# ArmBoard.net
KiCad netlist of a schematic drawn in Altium Designer
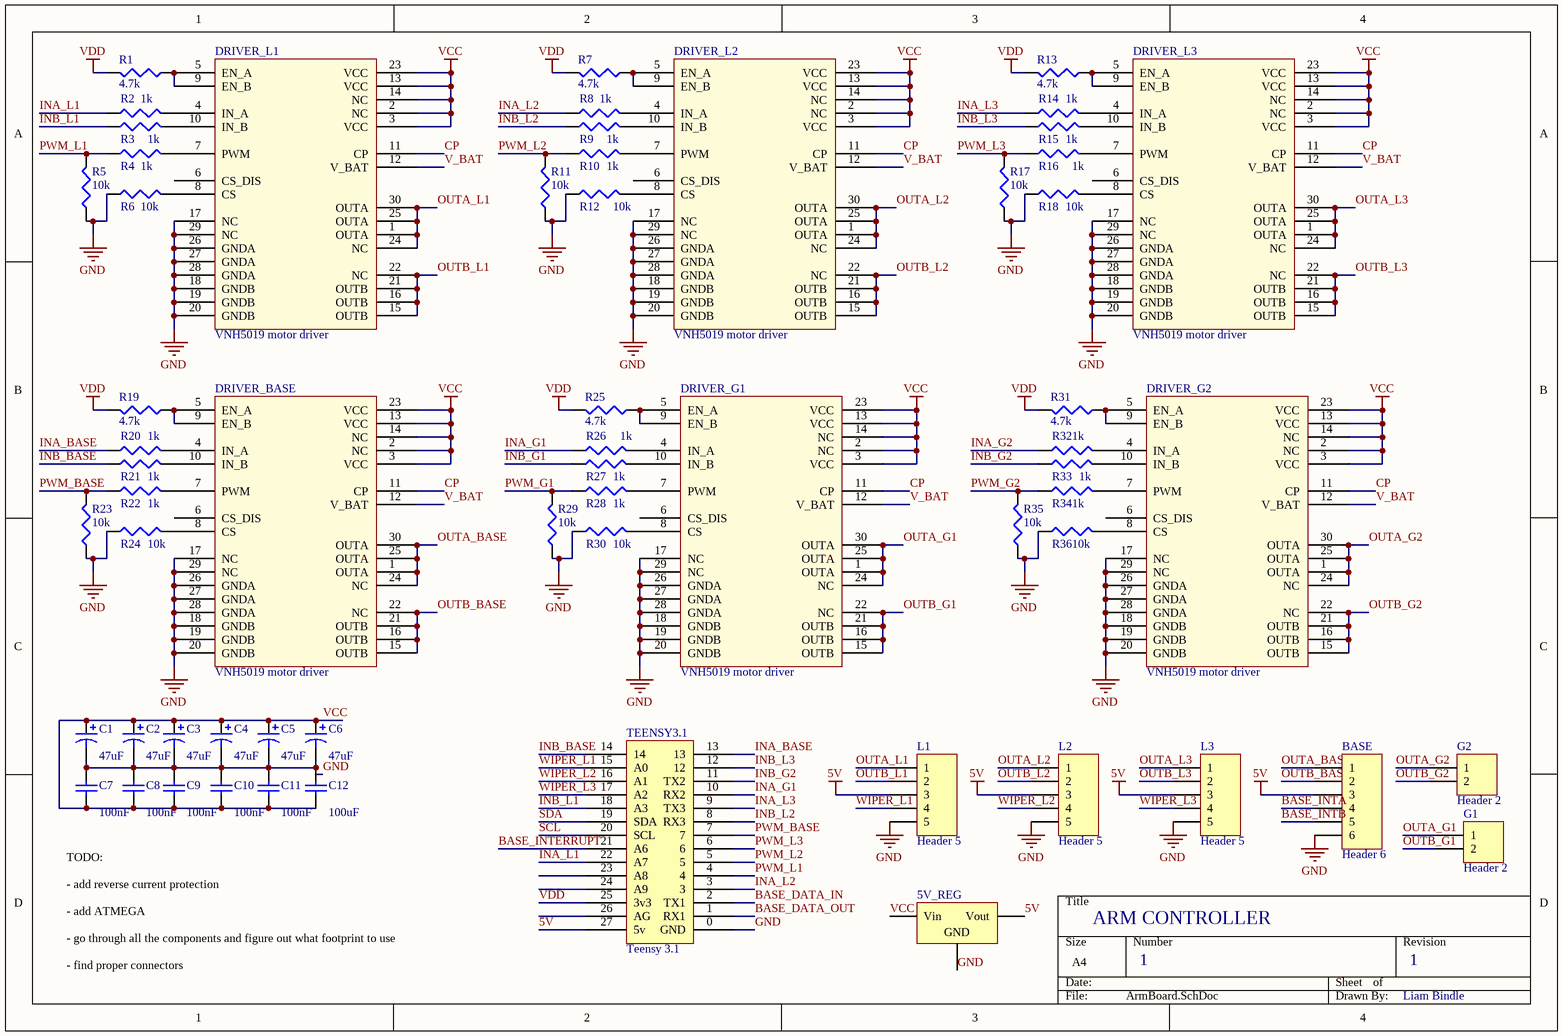
[diagram p0: ArmBoard.SchDoc]

(export (version "E")
  (design (tool "Eeschema 10.0.6"))
  (components
    (comp (ref "5V_REG")
      (value "~")
      (footprint "D2PAK_M")
      (description "Voltage Regulator")
      (fields (field (name "PUBLISHER") "Altium Limited"))
      (libsource (lib "Miscellaneous Devices") (part "Volt Reg"))
    )
    (comp (ref "BASE")
      (value "Header 6")
      (footprint "HDR1X6")
      (description "Header, 6-Pin")
      (fields (field (name "PUBLISHER") "Altium Limited"))
      (libsource (lib "Miscellaneous Connectors") (part "Header 6"))
    )
    (comp (ref "C1")
      (value "47uF")
      (footprint "RB7.6-15")
      (description "Polarized Capacitor (Radial)")
      (fields (field (name "PUBLISHER") "Altium Limited"))
      (libsource (lib "Miscellaneous Devices") (part "Cap Pol1"))
    )
    (comp (ref "C2")
      (value "47uF")
      (footprint "RB7.6-15")
      (description "Polarized Capacitor (Radial)")
      (fields (field (name "PUBLISHER") "Altium Limited"))
      (libsource (lib "Miscellaneous Devices") (part "Cap Pol1"))
    )
    (comp (ref "C3")
      (value "47uF")
      (footprint "RB7.6-15")
      (description "Polarized Capacitor (Radial)")
      (fields (field (name "PUBLISHER") "Altium Limited"))
      (libsource (lib "Miscellaneous Devices") (part "Cap Pol1"))
    )
    (comp (ref "C4")
      (value "47uF")
      (footprint "RB7.6-15")
      (description "Polarized Capacitor (Radial)")
      (fields (field (name "PUBLISHER") "Altium Limited"))
      (libsource (lib "Miscellaneous Devices") (part "Cap Pol1"))
    )
    (comp (ref "C5")
      (value "47uF")
      (footprint "RB7.6-15")
      (description "Polarized Capacitor (Radial)")
      (fields (field (name "PUBLISHER") "Altium Limited"))
      (libsource (lib "Miscellaneous Devices") (part "Cap Pol1"))
    )
    (comp (ref "C6")
      (value "47uF")
      (footprint "RB7.6-15")
      (description "Polarized Capacitor (Radial)")
      (fields (field (name "PUBLISHER") "Altium Limited"))
      (libsource (lib "Miscellaneous Devices") (part "Cap Pol1"))
    )
    (comp (ref "C7")
      (value "100nF")
      (footprint "RAD-0.3")
      (description "Capacitor")
      (fields (field (name "PUBLISHER") "Altium Limited"))
      (libsource (lib "Miscellaneous Devices") (part "Cap"))
    )
    (comp (ref "C8")
      (value "100nF")
      (footprint "RAD-0.3")
      (description "Capacitor")
      (fields (field (name "PUBLISHER") "Altium Limited"))
      (libsource (lib "Miscellaneous Devices") (part "Cap"))
    )
    (comp (ref "C9")
      (value "100nF")
      (footprint "RAD-0.3")
      (description "Capacitor")
      (fields (field (name "PUBLISHER") "Altium Limited"))
      (libsource (lib "Miscellaneous Devices") (part "Cap"))
    )
    (comp (ref "C10")
      (value "100nF")
      (footprint "RAD-0.3")
      (description "Capacitor")
      (fields (field (name "PUBLISHER") "Altium Limited"))
      (libsource (lib "Miscellaneous Devices") (part "Cap"))
    )
    (comp (ref "C11")
      (value "100nF")
      (footprint "RAD-0.3")
      (description "Capacitor")
      (fields (field (name "PUBLISHER") "Altium Limited"))
      (libsource (lib "Miscellaneous Devices") (part "Cap"))
    )
    (comp (ref "C12")
      (value "100uF")
      (footprint "RAD-0.3")
      (description "Capacitor")
      (fields (field (name "PUBLISHER") "Altium Limited"))
      (libsource (lib "Miscellaneous Devices") (part "Cap"))
    )
    (comp (ref "DRIVER_BASE")
      (value "VNH5019 motor driver")
      (footprint "VNH5019")
      (description "Motor driver")
      (libsource (lib "USSTParts") (part "VNH5019"))
    )
    (comp (ref "DRIVER_G1")
      (value "VNH5019 motor driver")
      (footprint "VNH5019")
      (description "Motor driver")
      (libsource (lib "USSTParts") (part "VNH5019"))
    )
    (comp (ref "DRIVER_G2")
      (value "VNH5019 motor driver")
      (footprint "VNH5019")
      (description "Motor driver")
      (libsource (lib "USSTParts") (part "VNH5019"))
    )
    (comp (ref "DRIVER_L1")
      (value "VNH5019 motor driver")
      (footprint "VNH5019")
      (description "Motor driver")
      (libsource (lib "USSTParts") (part "VNH5019"))
    )
    (comp (ref "DRIVER_L2")
      (value "VNH5019 motor driver")
      (footprint "VNH5019")
      (description "Motor driver")
      (libsource (lib "USSTParts") (part "VNH5019"))
    )
    (comp (ref "DRIVER_L3")
      (value "VNH5019 motor driver")
      (footprint "VNH5019")
      (description "Motor driver")
      (libsource (lib "USSTParts") (part "VNH5019"))
    )
    (comp (ref "G1")
      (value "Header 2")
      (footprint "HDR1X2")
      (description "Header, 2-Pin")
      (fields (field (name "PUBLISHER") "Altium Limited"))
      (libsource (lib "Miscellaneous Connectors") (part "Header 2"))
    )
    (comp (ref "G2")
      (value "Header 2")
      (footprint "HDR1X2")
      (description "Header, 2-Pin")
      (fields (field (name "PUBLISHER") "Altium Limited"))
      (libsource (lib "Miscellaneous Connectors") (part "Header 2"))
    )
    (comp (ref "L1")
      (value "Header 5")
      (footprint "HDR1X5")
      (description "Header, 5-Pin")
      (fields (field (name "PUBLISHER") "Altium Limited"))
      (libsource (lib "Miscellaneous Connectors") (part "Header 5"))
    )
    (comp (ref "L2")
      (value "Header 5")
      (footprint "HDR1X5")
      (description "Header, 5-Pin")
      (fields (field (name "PUBLISHER") "Altium Limited"))
      (libsource (lib "Miscellaneous Connectors") (part "Header 5"))
    )
    (comp (ref "L3")
      (value "Header 5")
      (footprint "HDR1X5")
      (description "Header, 5-Pin")
      (fields (field (name "PUBLISHER") "Altium Limited"))
      (libsource (lib "Miscellaneous Connectors") (part "Header 5"))
    )
    (comp (ref "R1")
      (value "4.7k")
      (footprint "J1-0603")
      (description "Resistor")
      (fields (field (name "Comment") "Res3") (field (name "PUBLISHER") "Altium Limited"))
      (libsource (lib "Miscellaneous Devices") (part "Res3"))
    )
    (comp (ref "R2")
      (value "1k")
      (footprint "J1-0603")
      (description "Resistor")
      (fields (field (name "Comment") "Res3") (field (name "PUBLISHER") "Altium Limited"))
      (libsource (lib "Miscellaneous Devices") (part "Res3"))
    )
    (comp (ref "R3")
      (value "1k")
      (footprint "J1-0603")
      (description "Resistor")
      (fields (field (name "Comment") "Res3") (field (name "PUBLISHER") "Altium Limited"))
      (libsource (lib "Miscellaneous Devices") (part "Res3"))
    )
    (comp (ref "R4")
      (value "1k")
      (footprint "J1-0603")
      (description "Resistor")
      (fields (field (name "Comment") "Res3") (field (name "PUBLISHER") "Altium Limited"))
      (libsource (lib "Miscellaneous Devices") (part "Res3"))
    )
    (comp (ref "R5")
      (value "10k")
      (footprint "J1-0603")
      (description "Resistor")
      (fields (field (name "Comment") "Res3") (field (name "PUBLISHER") "Altium Limited"))
      (libsource (lib "Miscellaneous Devices") (part "Res3"))
    )
    (comp (ref "R6")
      (value "10k")
      (footprint "J1-0603")
      (description "Resistor")
      (fields (field (name "Comment") "Res3") (field (name "PUBLISHER") "Altium Limited"))
      (libsource (lib "Miscellaneous Devices") (part "Res3"))
    )
    (comp (ref "R7")
      (value "4.7k")
      (footprint "J1-0603")
      (description "Resistor")
      (fields (field (name "Comment") "Res3") (field (name "PUBLISHER") "Altium Limited"))
      (libsource (lib "Miscellaneous Devices") (part "Res3"))
    )
    (comp (ref "R8")
      (value "1k")
      (footprint "J1-0603")
      (description "Resistor")
      (fields (field (name "Comment") "Res3") (field (name "PUBLISHER") "Altium Limited"))
      (libsource (lib "Miscellaneous Devices") (part "Res3"))
    )
    (comp (ref "R9")
      (value "1k")
      (footprint "J1-0603")
      (description "Resistor")
      (fields (field (name "Comment") "Res3") (field (name "PUBLISHER") "Altium Limited"))
      (libsource (lib "Miscellaneous Devices") (part "Res3"))
    )
    (comp (ref "R10")
      (value "1k")
      (footprint "J1-0603")
      (description "Resistor")
      (fields (field (name "Comment") "Res3") (field (name "PUBLISHER") "Altium Limited"))
      (libsource (lib "Miscellaneous Devices") (part "Res3"))
    )
    (comp (ref "R11")
      (value "10k")
      (footprint "J1-0603")
      (description "Resistor")
      (fields (field (name "Comment") "Res3") (field (name "PUBLISHER") "Altium Limited"))
      (libsource (lib "Miscellaneous Devices") (part "Res3"))
    )
    (comp (ref "R12")
      (value "10k")
      (footprint "J1-0603")
      (description "Resistor")
      (fields (field (name "Comment") "Res3") (field (name "PUBLISHER") "Altium Limited"))
      (libsource (lib "Miscellaneous Devices") (part "Res3"))
    )
    (comp (ref "R13")
      (value "4.7k")
      (footprint "J1-0603")
      (description "Resistor")
      (fields (field (name "Comment") "Res3") (field (name "PUBLISHER") "Altium Limited"))
      (libsource (lib "Miscellaneous Devices") (part "Res3"))
    )
    (comp (ref "R14")
      (value "1k")
      (footprint "J1-0603")
      (description "Resistor")
      (fields (field (name "Comment") "Res3") (field (name "PUBLISHER") "Altium Limited"))
      (libsource (lib "Miscellaneous Devices") (part "Res3"))
    )
    (comp (ref "R15")
      (value "1k")
      (footprint "J1-0603")
      (description "Resistor")
      (fields (field (name "Comment") "Res3") (field (name "PUBLISHER") "Altium Limited"))
      (libsource (lib "Miscellaneous Devices") (part "Res3"))
    )
    (comp (ref "R16")
      (value "1k")
      (footprint "J1-0603")
      (description "Resistor")
      (fields (field (name "Comment") "Res3") (field (name "PUBLISHER") "Altium Limited"))
      (libsource (lib "Miscellaneous Devices") (part "Res3"))
    )
    (comp (ref "R17")
      (value "10k")
      (footprint "J1-0603")
      (description "Resistor")
      (fields (field (name "Comment") "Res3") (field (name "PUBLISHER") "Altium Limited"))
      (libsource (lib "Miscellaneous Devices") (part "Res3"))
    )
    (comp (ref "R18")
      (value "10k")
      (footprint "J1-0603")
      (description "Resistor")
      (fields (field (name "Comment") "Res3") (field (name "PUBLISHER") "Altium Limited"))
      (libsource (lib "Miscellaneous Devices") (part "Res3"))
    )
    (comp (ref "R19")
      (value "4.7k")
      (footprint "J1-0603")
      (description "Resistor")
      (fields (field (name "Comment") "Res3") (field (name "PUBLISHER") "Altium Limited"))
      (libsource (lib "Miscellaneous Devices") (part "Res3"))
    )
    (comp (ref "R20")
      (value "1k")
      (footprint "J1-0603")
      (description "Resistor")
      (fields (field (name "Comment") "Res3") (field (name "PUBLISHER") "Altium Limited"))
      (libsource (lib "Miscellaneous Devices") (part "Res3"))
    )
    (comp (ref "R21")
      (value "1k")
      (footprint "J1-0603")
      (description "Resistor")
      (fields (field (name "Comment") "Res3") (field (name "PUBLISHER") "Altium Limited"))
      (libsource (lib "Miscellaneous Devices") (part "Res3"))
    )
    (comp (ref "R22")
      (value "1k")
      (footprint "J1-0603")
      (description "Resistor")
      (fields (field (name "Comment") "Res3") (field (name "PUBLISHER") "Altium Limited"))
      (libsource (lib "Miscellaneous Devices") (part "Res3"))
    )
    (comp (ref "R23")
      (value "10k")
      (footprint "J1-0603")
      (description "Resistor")
      (fields (field (name "Comment") "Res3") (field (name "PUBLISHER") "Altium Limited"))
      (libsource (lib "Miscellaneous Devices") (part "Res3"))
    )
    (comp (ref "R24")
      (value "10k")
      (footprint "J1-0603")
      (description "Resistor")
      (fields (field (name "Comment") "Res3") (field (name "PUBLISHER") "Altium Limited"))
      (libsource (lib "Miscellaneous Devices") (part "Res3"))
    )
    (comp (ref "R25")
      (value "4.7k")
      (footprint "J1-0603")
      (description "Resistor")
      (fields (field (name "Comment") "Res3") (field (name "PUBLISHER") "Altium Limited"))
      (libsource (lib "Miscellaneous Devices") (part "Res3"))
    )
    (comp (ref "R26")
      (value "1k")
      (footprint "J1-0603")
      (description "Resistor")
      (fields (field (name "Comment") "Res3") (field (name "PUBLISHER") "Altium Limited"))
      (libsource (lib "Miscellaneous Devices") (part "Res3"))
    )
    (comp (ref "R27")
      (value "1k")
      (footprint "J1-0603")
      (description "Resistor")
      (fields (field (name "Comment") "Res3") (field (name "PUBLISHER") "Altium Limited"))
      (libsource (lib "Miscellaneous Devices") (part "Res3"))
    )
    (comp (ref "R28")
      (value "1k")
      (footprint "J1-0603")
      (description "Resistor")
      (fields (field (name "Comment") "Res3") (field (name "PUBLISHER") "Altium Limited"))
      (libsource (lib "Miscellaneous Devices") (part "Res3"))
    )
    (comp (ref "R29")
      (value "10k")
      (footprint "J1-0603")
      (description "Resistor")
      (fields (field (name "Comment") "Res3") (field (name "PUBLISHER") "Altium Limited"))
      (libsource (lib "Miscellaneous Devices") (part "Res3"))
    )
    (comp (ref "R30")
      (value "10k")
      (footprint "J1-0603")
      (description "Resistor")
      (fields (field (name "Comment") "Res3") (field (name "PUBLISHER") "Altium Limited"))
      (libsource (lib "Miscellaneous Devices") (part "Res3"))
    )
    (comp (ref "R31")
      (value "4.7k")
      (footprint "J1-0603")
      (description "Resistor")
      (fields (field (name "Comment") "Res3") (field (name "PUBLISHER") "Altium Limited"))
      (libsource (lib "Miscellaneous Devices") (part "Res3"))
    )
    (comp (ref "R32")
      (value "1k")
      (footprint "J1-0603")
      (description "Resistor")
      (fields (field (name "Comment") "Res3") (field (name "PUBLISHER") "Altium Limited"))
      (libsource (lib "Miscellaneous Devices") (part "Res3"))
    )
    (comp (ref "R33")
      (value "1k")
      (footprint "J1-0603")
      (description "Resistor")
      (fields (field (name "Comment") "Res3") (field (name "PUBLISHER") "Altium Limited"))
      (libsource (lib "Miscellaneous Devices") (part "Res3"))
    )
    (comp (ref "R34")
      (value "1k")
      (footprint "J1-0603")
      (description "Resistor")
      (fields (field (name "Comment") "Res3") (field (name "PUBLISHER") "Altium Limited"))
      (libsource (lib "Miscellaneous Devices") (part "Res3"))
    )
    (comp (ref "R35")
      (value "10k")
      (footprint "J1-0603")
      (description "Resistor")
      (fields (field (name "Comment") "Res3") (field (name "PUBLISHER") "Altium Limited"))
      (libsource (lib "Miscellaneous Devices") (part "Res3"))
    )
    (comp (ref "R36")
      (value "10k")
      (footprint "J1-0603")
      (description "Resistor")
      (fields (field (name "Comment") "Res3") (field (name "PUBLISHER") "Altium Limited"))
      (libsource (lib "Miscellaneous Devices") (part "Res3"))
    )
    (comp (ref "TEENSY3.1")
      (value "Teensy 3.1")
      (footprint "TEENSY3.1")
      (libsource (lib "USST2016") (part "Teensy 3.1"))
    )
  )
  (nets
    (net (code "1") (name "/BASE_DATA_IN") (class "Default")
      (node (ref "TEENSY3.1") (pin "2") (pinfunction "TX1_2") (pintype "passive"))
    )
    (net (code "2") (name "/BASE_DATA_OUT") (class "Default")
      (node (ref "TEENSY3.1") (pin "1") (pinfunction "RX1_1") (pintype "passive"))
    )
    (net (code "3") (name "/BASE_INTA") (class "Default")
      (node (ref "BASE") (pin "4") (pinfunction "4_4") (pintype "passive"))
    )
    (net (code "4") (name "/BASE_INTB") (class "Default")
      (node (ref "BASE") (pin "5") (pinfunction "5_5") (pintype "passive"))
    )
    (net (code "5") (name "/BASE_INTERRUPT") (class "Default")
      (node (ref "TEENSY3.1") (pin "21") (pinfunction "A6_21") (pintype "passive"))
    )
    (net (code "6") (name "/CP") (class "Default")
      (node (ref "DRIVER_BASE") (pin "11") (pinfunction "CP_11") (pintype "passive"))
      (node (ref "DRIVER_G1") (pin "11") (pinfunction "CP_11") (pintype "passive"))
      (node (ref "DRIVER_G2") (pin "11") (pinfunction "CP_11") (pintype "passive"))
      (node (ref "DRIVER_L1") (pin "11") (pinfunction "CP_11") (pintype "passive"))
      (node (ref "DRIVER_L2") (pin "11") (pinfunction "CP_11") (pintype "passive"))
      (node (ref "DRIVER_L3") (pin "11") (pinfunction "CP_11") (pintype "passive"))
    )
    (net (code "7") (name "/INA_BASE") (class "Default")
      (node (ref "R20") (pin "1") (pinfunction "1_1") (pintype "passive"))
      (node (ref "TEENSY3.1") (pin "13") (pinfunction "13_13") (pintype "passive"))
    )
    (net (code "8") (name "/INA_G1") (class "Default")
      (node (ref "R26") (pin "1") (pinfunction "1_1") (pintype "passive"))
      (node (ref "TEENSY3.1") (pin "10") (pinfunction "RX2_10") (pintype "passive"))
    )
    (net (code "9") (name "/INA_G2") (class "Default")
      (node (ref "R32") (pin "1") (pinfunction "1_1") (pintype "passive"))
    )
    (net (code "10") (name "/INA_L1") (class "Default")
      (node (ref "R2") (pin "1") (pinfunction "1_1") (pintype "passive"))
      (node (ref "TEENSY3.1") (pin "22") (pinfunction "A7_22") (pintype "passive"))
    )
    (net (code "11") (name "/INA_L2") (class "Default")
      (node (ref "R8") (pin "1") (pinfunction "1_1") (pintype "passive"))
      (node (ref "TEENSY3.1") (pin "3") (pinfunction "3_3") (pintype "passive"))
    )
    (net (code "12") (name "/INA_L3") (class "Default")
      (node (ref "R14") (pin "1") (pinfunction "1_1") (pintype "passive"))
      (node (ref "TEENSY3.1") (pin "9") (pinfunction "TX3_9") (pintype "passive"))
    )
    (net (code "13") (name "/INB_BASE") (class "Default")
      (node (ref "R21") (pin "1") (pinfunction "1_1") (pintype "passive"))
      (node (ref "TEENSY3.1") (pin "14") (pinfunction "14_14") (pintype "passive"))
    )
    (net (code "14") (name "/INB_G1") (class "Default")
      (node (ref "R27") (pin "1") (pinfunction "1_1") (pintype "passive"))
    )
    (net (code "15") (name "/INB_G2") (class "Default")
      (node (ref "R33") (pin "1") (pinfunction "1_1") (pintype "passive"))
      (node (ref "TEENSY3.1") (pin "11") (pinfunction "TX2_11") (pintype "passive"))
    )
    (net (code "16") (name "/INB_L1") (class "Default")
      (node (ref "R3") (pin "1") (pinfunction "1_1") (pintype "passive"))
      (node (ref "TEENSY3.1") (pin "18") (pinfunction "A3_18") (pintype "passive"))
    )
    (net (code "17") (name "/INB_L2") (class "Default")
      (node (ref "R9") (pin "1") (pinfunction "1_1") (pintype "passive"))
      (node (ref "TEENSY3.1") (pin "8") (pinfunction "RX3_8") (pintype "passive"))
    )
    (net (code "18") (name "/INB_L3") (class "Default")
      (node (ref "R15") (pin "1") (pinfunction "1_1") (pintype "passive"))
      (node (ref "TEENSY3.1") (pin "12") (pinfunction "12_12") (pintype "passive"))
    )
    (net (code "19") (name "/OUTA_BASE") (class "Default")
      (node (ref "BASE") (pin "1") (pinfunction "1_1") (pintype "passive"))
      (node (ref "DRIVER_BASE") (pin "1") (pinfunction "OUTA_1") (pintype "passive"))
      (node (ref "DRIVER_BASE") (pin "24") (pinfunction "NC_24") (pintype "passive"))
      (node (ref "DRIVER_BASE") (pin "25") (pinfunction "OUTA_25") (pintype "passive"))
      (node (ref "DRIVER_BASE") (pin "30") (pinfunction "OUTA_30") (pintype "passive"))
    )
    (net (code "20") (name "/OUTA_G1") (class "Default")
      (node (ref "DRIVER_G1") (pin "1") (pinfunction "OUTA_1") (pintype "passive"))
      (node (ref "DRIVER_G1") (pin "24") (pinfunction "NC_24") (pintype "passive"))
      (node (ref "DRIVER_G1") (pin "25") (pinfunction "OUTA_25") (pintype "passive"))
      (node (ref "DRIVER_G1") (pin "30") (pinfunction "OUTA_30") (pintype "passive"))
      (node (ref "G1") (pin "1") (pinfunction "1_1") (pintype "passive"))
    )
    (net (code "21") (name "/OUTA_G2") (class "Default")
      (node (ref "DRIVER_G2") (pin "1") (pinfunction "OUTA_1") (pintype "passive"))
      (node (ref "DRIVER_G2") (pin "24") (pinfunction "NC_24") (pintype "passive"))
      (node (ref "DRIVER_G2") (pin "25") (pinfunction "OUTA_25") (pintype "passive"))
      (node (ref "DRIVER_G2") (pin "30") (pinfunction "OUTA_30") (pintype "passive"))
      (node (ref "G2") (pin "1") (pinfunction "1_1") (pintype "passive"))
    )
    (net (code "22") (name "/OUTA_L1") (class "Default")
      (node (ref "DRIVER_L1") (pin "1") (pinfunction "OUTA_1") (pintype "passive"))
      (node (ref "DRIVER_L1") (pin "24") (pinfunction "NC_24") (pintype "passive"))
      (node (ref "DRIVER_L1") (pin "25") (pinfunction "OUTA_25") (pintype "passive"))
      (node (ref "DRIVER_L1") (pin "30") (pinfunction "OUTA_30") (pintype "passive"))
      (node (ref "L1") (pin "1") (pinfunction "1_1") (pintype "passive"))
    )
    (net (code "23") (name "/OUTA_L2") (class "Default")
      (node (ref "DRIVER_L2") (pin "1") (pinfunction "OUTA_1") (pintype "passive"))
      (node (ref "DRIVER_L2") (pin "24") (pinfunction "NC_24") (pintype "passive"))
      (node (ref "DRIVER_L2") (pin "25") (pinfunction "OUTA_25") (pintype "passive"))
      (node (ref "DRIVER_L2") (pin "30") (pinfunction "OUTA_30") (pintype "passive"))
      (node (ref "L2") (pin "1") (pinfunction "1_1") (pintype "passive"))
    )
    (net (code "24") (name "/OUTA_L3") (class "Default")
      (node (ref "DRIVER_L3") (pin "1") (pinfunction "OUTA_1") (pintype "passive"))
      (node (ref "DRIVER_L3") (pin "24") (pinfunction "NC_24") (pintype "passive"))
      (node (ref "DRIVER_L3") (pin "25") (pinfunction "OUTA_25") (pintype "passive"))
      (node (ref "DRIVER_L3") (pin "30") (pinfunction "OUTA_30") (pintype "passive"))
      (node (ref "L3") (pin "1") (pinfunction "1_1") (pintype "passive"))
    )
    (net (code "25") (name "/OUTB_BASE") (class "Default")
      (node (ref "BASE") (pin "2") (pinfunction "2_2") (pintype "passive"))
      (node (ref "DRIVER_BASE") (pin "15") (pinfunction "OUTB_15") (pintype "passive"))
      (node (ref "DRIVER_BASE") (pin "16") (pinfunction "OUTB_16") (pintype "passive"))
      (node (ref "DRIVER_BASE") (pin "21") (pinfunction "OUTB_21") (pintype "passive"))
      (node (ref "DRIVER_BASE") (pin "22") (pinfunction "NC_22") (pintype "passive"))
    )
    (net (code "26") (name "/OUTB_G1") (class "Default")
      (node (ref "DRIVER_G1") (pin "15") (pinfunction "OUTB_15") (pintype "passive"))
      (node (ref "DRIVER_G1") (pin "16") (pinfunction "OUTB_16") (pintype "passive"))
      (node (ref "DRIVER_G1") (pin "21") (pinfunction "OUTB_21") (pintype "passive"))
      (node (ref "DRIVER_G1") (pin "22") (pinfunction "NC_22") (pintype "passive"))
      (node (ref "G1") (pin "2") (pinfunction "2_2") (pintype "passive"))
    )
    (net (code "27") (name "/OUTB_G2") (class "Default")
      (node (ref "DRIVER_G2") (pin "15") (pinfunction "OUTB_15") (pintype "passive"))
      (node (ref "DRIVER_G2") (pin "16") (pinfunction "OUTB_16") (pintype "passive"))
      (node (ref "DRIVER_G2") (pin "21") (pinfunction "OUTB_21") (pintype "passive"))
      (node (ref "DRIVER_G2") (pin "22") (pinfunction "NC_22") (pintype "passive"))
      (node (ref "G2") (pin "2") (pinfunction "2_2") (pintype "passive"))
    )
    (net (code "28") (name "/OUTB_L1") (class "Default")
      (node (ref "DRIVER_L1") (pin "15") (pinfunction "OUTB_15") (pintype "passive"))
      (node (ref "DRIVER_L1") (pin "16") (pinfunction "OUTB_16") (pintype "passive"))
      (node (ref "DRIVER_L1") (pin "21") (pinfunction "OUTB_21") (pintype "passive"))
      (node (ref "DRIVER_L1") (pin "22") (pinfunction "NC_22") (pintype "passive"))
      (node (ref "L1") (pin "2") (pinfunction "2_2") (pintype "passive"))
    )
    (net (code "29") (name "/OUTB_L2") (class "Default")
      (node (ref "DRIVER_L2") (pin "15") (pinfunction "OUTB_15") (pintype "passive"))
      (node (ref "DRIVER_L2") (pin "16") (pinfunction "OUTB_16") (pintype "passive"))
      (node (ref "DRIVER_L2") (pin "21") (pinfunction "OUTB_21") (pintype "passive"))
      (node (ref "DRIVER_L2") (pin "22") (pinfunction "NC_22") (pintype "passive"))
      (node (ref "L2") (pin "2") (pinfunction "2_2") (pintype "passive"))
    )
    (net (code "30") (name "/OUTB_L3") (class "Default")
      (node (ref "DRIVER_L3") (pin "15") (pinfunction "OUTB_15") (pintype "passive"))
      (node (ref "DRIVER_L3") (pin "16") (pinfunction "OUTB_16") (pintype "passive"))
      (node (ref "DRIVER_L3") (pin "21") (pinfunction "OUTB_21") (pintype "passive"))
      (node (ref "DRIVER_L3") (pin "22") (pinfunction "NC_22") (pintype "passive"))
      (node (ref "L3") (pin "2") (pinfunction "2_2") (pintype "passive"))
    )
    (net (code "31") (name "/PWM_BASE") (class "Default")
      (node (ref "R22") (pin "1") (pinfunction "1_1") (pintype "passive"))
      (node (ref "R23") (pin "2") (pinfunction "2_2") (pintype "passive"))
      (node (ref "TEENSY3.1") (pin "7") (pinfunction "7_7") (pintype "passive"))
    )
    (net (code "32") (name "/PWM_G1") (class "Default")
      (node (ref "R28") (pin "1") (pinfunction "1_1") (pintype "passive"))
      (node (ref "R29") (pin "2") (pinfunction "2_2") (pintype "passive"))
    )
    (net (code "33") (name "/PWM_G2") (class "Default")
      (node (ref "R34") (pin "1") (pinfunction "1_1") (pintype "passive"))
      (node (ref "R35") (pin "2") (pinfunction "2_2") (pintype "passive"))
    )
    (net (code "34") (name "/PWM_L1") (class "Default")
      (node (ref "R4") (pin "1") (pinfunction "1_1") (pintype "passive"))
      (node (ref "R5") (pin "2") (pinfunction "2_2") (pintype "passive"))
      (node (ref "TEENSY3.1") (pin "4") (pinfunction "4_4") (pintype "passive"))
    )
    (net (code "35") (name "/PWM_L2") (class "Default")
      (node (ref "R10") (pin "1") (pinfunction "1_1") (pintype "passive"))
      (node (ref "R11") (pin "2") (pinfunction "2_2") (pintype "passive"))
      (node (ref "TEENSY3.1") (pin "5") (pinfunction "5_5") (pintype "passive"))
    )
    (net (code "36") (name "/PWM_L3") (class "Default")
      (node (ref "R16") (pin "1") (pinfunction "1_1") (pintype "passive"))
      (node (ref "R17") (pin "2") (pinfunction "2_2") (pintype "passive"))
      (node (ref "TEENSY3.1") (pin "6") (pinfunction "6_6") (pintype "passive"))
    )
    (net (code "37") (name "/SCL") (class "Default")
      (node (ref "TEENSY3.1") (pin "20") (pinfunction "SCL_20") (pintype "passive"))
    )
    (net (code "38") (name "/SDA") (class "Default")
      (node (ref "TEENSY3.1") (pin "19") (pinfunction "SDA_19") (pintype "passive"))
    )
    (net (code "39") (name "/V_BAT") (class "Default")
      (node (ref "DRIVER_BASE") (pin "12") (pinfunction "V_BAT_12") (pintype "passive"))
      (node (ref "DRIVER_G1") (pin "12") (pinfunction "V_BAT_12") (pintype "passive"))
      (node (ref "DRIVER_G2") (pin "12") (pinfunction "V_BAT_12") (pintype "passive"))
      (node (ref "DRIVER_L1") (pin "12") (pinfunction "V_BAT_12") (pintype "passive"))
      (node (ref "DRIVER_L2") (pin "12") (pinfunction "V_BAT_12") (pintype "passive"))
      (node (ref "DRIVER_L3") (pin "12") (pinfunction "V_BAT_12") (pintype "passive"))
    )
    (net (code "40") (name "/WIPER_L1") (class "Default")
      (node (ref "L1") (pin "4") (pinfunction "4_4") (pintype "passive"))
      (node (ref "TEENSY3.1") (pin "15") (pinfunction "A0_15") (pintype "passive"))
    )
    (net (code "41") (name "/WIPER_L2") (class "Default")
      (node (ref "L2") (pin "4") (pinfunction "4_4") (pintype "passive"))
      (node (ref "TEENSY3.1") (pin "16") (pinfunction "A1_16") (pintype "passive"))
    )
    (net (code "42") (name "/WIPER_L3") (class "Default")
      (node (ref "L3") (pin "4") (pinfunction "4_4") (pintype "passive"))
      (node (ref "TEENSY3.1") (pin "17") (pinfunction "A2_17") (pintype "passive"))
    )
    (net (code "43") (name "5V") (class "Default")
      (node (ref "5V_REG") (pin "3") (pinfunction "Vout_3") (pintype "passive"))
      (node (ref "BASE") (pin "3") (pinfunction "3_3") (pintype "passive"))
      (node (ref "L1") (pin "3") (pinfunction "3_3") (pintype "passive"))
      (node (ref "L2") (pin "3") (pinfunction "3_3") (pintype "passive"))
      (node (ref "L3") (pin "3") (pinfunction "3_3") (pintype "passive"))
      (node (ref "TEENSY3.1") (pin "27") (pinfunction "5v_27") (pintype "passive"))
    )
    (net (code "44") (name "GND") (class "Default")
      (node (ref "5V_REG") (pin "2") (pinfunction "GND_2") (pintype "passive"))
      (node (ref "BASE") (pin "6") (pinfunction "6_6") (pintype "passive"))
      (node (ref "C1") (pin "2") (pinfunction "2_2") (pintype "passive"))
      (node (ref "C10") (pin "2") (pinfunction "2_2") (pintype "passive"))
      (node (ref "C11") (pin "2") (pinfunction "2_2") (pintype "passive"))
      (node (ref "C12") (pin "2") (pinfunction "2_2") (pintype "passive"))
      (node (ref "C2") (pin "2") (pinfunction "2_2") (pintype "passive"))
      (node (ref "C3") (pin "2") (pinfunction "2_2") (pintype "passive"))
      (node (ref "C4") (pin "2") (pinfunction "2_2") (pintype "passive"))
      (node (ref "C5") (pin "2") (pinfunction "2_2") (pintype "passive"))
      (node (ref "C6") (pin "2") (pinfunction "2_2") (pintype "passive"))
      (node (ref "C7") (pin "2") (pinfunction "2_2") (pintype "passive"))
      (node (ref "C8") (pin "2") (pinfunction "2_2") (pintype "passive"))
      (node (ref "C9") (pin "2") (pinfunction "2_2") (pintype "passive"))
      (node (ref "DRIVER_BASE") (pin "17") (pinfunction "NC_17") (pintype "passive"))
      (node (ref "DRIVER_BASE") (pin "18") (pinfunction "GNDB_18") (pintype "passive"))
      (node (ref "DRIVER_BASE") (pin "19") (pinfunction "GNDB_19") (pintype "passive"))
      (node (ref "DRIVER_BASE") (pin "20") (pinfunction "GNDB_20") (pintype "passive"))
      (node (ref "DRIVER_BASE") (pin "26") (pinfunction "GNDA_26") (pintype "passive"))
      (node (ref "DRIVER_BASE") (pin "27") (pinfunction "GNDA_27") (pintype "passive"))
      (node (ref "DRIVER_BASE") (pin "28") (pinfunction "GNDA_28") (pintype "passive"))
      (node (ref "DRIVER_BASE") (pin "29") (pinfunction "NC_29") (pintype "passive"))
      (node (ref "DRIVER_G1") (pin "17") (pinfunction "NC_17") (pintype "passive"))
      (node (ref "DRIVER_G1") (pin "18") (pinfunction "GNDB_18") (pintype "passive"))
      (node (ref "DRIVER_G1") (pin "19") (pinfunction "GNDB_19") (pintype "passive"))
      (node (ref "DRIVER_G1") (pin "20") (pinfunction "GNDB_20") (pintype "passive"))
      (node (ref "DRIVER_G1") (pin "26") (pinfunction "GNDA_26") (pintype "passive"))
      (node (ref "DRIVER_G1") (pin "27") (pinfunction "GNDA_27") (pintype "passive"))
      (node (ref "DRIVER_G1") (pin "28") (pinfunction "GNDA_28") (pintype "passive"))
      (node (ref "DRIVER_G1") (pin "29") (pinfunction "NC_29") (pintype "passive"))
      (node (ref "DRIVER_G2") (pin "17") (pinfunction "NC_17") (pintype "passive"))
      (node (ref "DRIVER_G2") (pin "18") (pinfunction "GNDB_18") (pintype "passive"))
      (node (ref "DRIVER_G2") (pin "19") (pinfunction "GNDB_19") (pintype "passive"))
      (node (ref "DRIVER_G2") (pin "20") (pinfunction "GNDB_20") (pintype "passive"))
      (node (ref "DRIVER_G2") (pin "26") (pinfunction "GNDA_26") (pintype "passive"))
      (node (ref "DRIVER_G2") (pin "27") (pinfunction "GNDA_27") (pintype "passive"))
      (node (ref "DRIVER_G2") (pin "28") (pinfunction "GNDA_28") (pintype "passive"))
      (node (ref "DRIVER_G2") (pin "29") (pinfunction "NC_29") (pintype "passive"))
      (node (ref "DRIVER_L1") (pin "17") (pinfunction "NC_17") (pintype "passive"))
      (node (ref "DRIVER_L1") (pin "18") (pinfunction "GNDB_18") (pintype "passive"))
      (node (ref "DRIVER_L1") (pin "19") (pinfunction "GNDB_19") (pintype "passive"))
      (node (ref "DRIVER_L1") (pin "20") (pinfunction "GNDB_20") (pintype "passive"))
      (node (ref "DRIVER_L1") (pin "26") (pinfunction "GNDA_26") (pintype "passive"))
      (node (ref "DRIVER_L1") (pin "27") (pinfunction "GNDA_27") (pintype "passive"))
      (node (ref "DRIVER_L1") (pin "28") (pinfunction "GNDA_28") (pintype "passive"))
      (node (ref "DRIVER_L1") (pin "29") (pinfunction "NC_29") (pintype "passive"))
      (node (ref "DRIVER_L2") (pin "17") (pinfunction "NC_17") (pintype "passive"))
      (node (ref "DRIVER_L2") (pin "18") (pinfunction "GNDB_18") (pintype "passive"))
      (node (ref "DRIVER_L2") (pin "19") (pinfunction "GNDB_19") (pintype "passive"))
      (node (ref "DRIVER_L2") (pin "20") (pinfunction "GNDB_20") (pintype "passive"))
      (node (ref "DRIVER_L2") (pin "26") (pinfunction "GNDA_26") (pintype "passive"))
      (node (ref "DRIVER_L2") (pin "27") (pinfunction "GNDA_27") (pintype "passive"))
      (node (ref "DRIVER_L2") (pin "28") (pinfunction "GNDA_28") (pintype "passive"))
      (node (ref "DRIVER_L2") (pin "29") (pinfunction "NC_29") (pintype "passive"))
      (node (ref "DRIVER_L3") (pin "17") (pinfunction "NC_17") (pintype "passive"))
      (node (ref "DRIVER_L3") (pin "18") (pinfunction "GNDB_18") (pintype "passive"))
      (node (ref "DRIVER_L3") (pin "19") (pinfunction "GNDB_19") (pintype "passive"))
      (node (ref "DRIVER_L3") (pin "20") (pinfunction "GNDB_20") (pintype "passive"))
      (node (ref "DRIVER_L3") (pin "26") (pinfunction "GNDA_26") (pintype "passive"))
      (node (ref "DRIVER_L3") (pin "27") (pinfunction "GNDA_27") (pintype "passive"))
      (node (ref "DRIVER_L3") (pin "28") (pinfunction "GNDA_28") (pintype "passive"))
      (node (ref "DRIVER_L3") (pin "29") (pinfunction "NC_29") (pintype "passive"))
      (node (ref "L1") (pin "5") (pinfunction "5_5") (pintype "passive"))
      (node (ref "L2") (pin "5") (pinfunction "5_5") (pintype "passive"))
      (node (ref "L3") (pin "5") (pinfunction "5_5") (pintype "passive"))
      (node (ref "R11") (pin "1") (pinfunction "1_1") (pintype "passive"))
      (node (ref "R12") (pin "1") (pinfunction "1_1") (pintype "passive"))
      (node (ref "R17") (pin "1") (pinfunction "1_1") (pintype "passive"))
      (node (ref "R18") (pin "1") (pinfunction "1_1") (pintype "passive"))
      (node (ref "R23") (pin "1") (pinfunction "1_1") (pintype "passive"))
      (node (ref "R24") (pin "1") (pinfunction "1_1") (pintype "passive"))
      (node (ref "R29") (pin "1") (pinfunction "1_1") (pintype "passive"))
      (node (ref "R30") (pin "1") (pinfunction "1_1") (pintype "passive"))
      (node (ref "R35") (pin "1") (pinfunction "1_1") (pintype "passive"))
      (node (ref "R36") (pin "1") (pinfunction "1_1") (pintype "passive"))
      (node (ref "R5") (pin "1") (pinfunction "1_1") (pintype "passive"))
      (node (ref "R6") (pin "1") (pinfunction "1_1") (pintype "passive"))
      (node (ref "TEENSY3.1") (pin "0") (pinfunction "GND_0") (pintype "passive"))
    )
    (net (code "45") (name "Net-(DRIVER_BASE-CS)") (class "Default")
      (node (ref "DRIVER_BASE") (pin "8") (pinfunction "CS_8") (pintype "passive"))
      (node (ref "R24") (pin "2") (pinfunction "2_2") (pintype "passive"))
    )
    (net (code "46") (name "Net-(DRIVER_BASE-EN_A)") (class "Default")
      (node (ref "DRIVER_BASE") (pin "5") (pinfunction "EN_A_5") (pintype "passive"))
      (node (ref "DRIVER_BASE") (pin "9") (pinfunction "EN_B_9") (pintype "passive"))
      (node (ref "R19") (pin "1") (pinfunction "1_1") (pintype "passive"))
    )
    (net (code "47") (name "Net-(DRIVER_BASE-IN_A)") (class "Default")
      (node (ref "DRIVER_BASE") (pin "4") (pinfunction "IN_A_4") (pintype "passive"))
      (node (ref "R20") (pin "2") (pinfunction "2_2") (pintype "passive"))
    )
    (net (code "48") (name "Net-(DRIVER_BASE-IN_B)") (class "Default")
      (node (ref "DRIVER_BASE") (pin "10") (pinfunction "IN_B_10") (pintype "passive"))
      (node (ref "R21") (pin "2") (pinfunction "2_2") (pintype "passive"))
    )
    (net (code "49") (name "Net-(DRIVER_BASE-PWM)") (class "Default")
      (node (ref "DRIVER_BASE") (pin "7") (pinfunction "PWM_7") (pintype "passive"))
      (node (ref "R22") (pin "2") (pinfunction "2_2") (pintype "passive"))
    )
    (net (code "50") (name "Net-(DRIVER_G1-CS)") (class "Default")
      (node (ref "DRIVER_G1") (pin "8") (pinfunction "CS_8") (pintype "passive"))
      (node (ref "R30") (pin "2") (pinfunction "2_2") (pintype "passive"))
    )
    (net (code "51") (name "Net-(DRIVER_G1-EN_A)") (class "Default")
      (node (ref "DRIVER_G1") (pin "5") (pinfunction "EN_A_5") (pintype "passive"))
      (node (ref "DRIVER_G1") (pin "9") (pinfunction "EN_B_9") (pintype "passive"))
      (node (ref "R25") (pin "1") (pinfunction "1_1") (pintype "passive"))
    )
    (net (code "52") (name "Net-(DRIVER_G1-IN_A)") (class "Default")
      (node (ref "DRIVER_G1") (pin "4") (pinfunction "IN_A_4") (pintype "passive"))
      (node (ref "R26") (pin "2") (pinfunction "2_2") (pintype "passive"))
    )
    (net (code "53") (name "Net-(DRIVER_G1-IN_B)") (class "Default")
      (node (ref "DRIVER_G1") (pin "10") (pinfunction "IN_B_10") (pintype "passive"))
      (node (ref "R27") (pin "2") (pinfunction "2_2") (pintype "passive"))
    )
    (net (code "54") (name "Net-(DRIVER_G1-PWM)") (class "Default")
      (node (ref "DRIVER_G1") (pin "7") (pinfunction "PWM_7") (pintype "passive"))
      (node (ref "R28") (pin "2") (pinfunction "2_2") (pintype "passive"))
    )
    (net (code "55") (name "Net-(DRIVER_G2-CS)") (class "Default")
      (node (ref "DRIVER_G2") (pin "8") (pinfunction "CS_8") (pintype "passive"))
      (node (ref "R36") (pin "2") (pinfunction "2_2") (pintype "passive"))
    )
    (net (code "56") (name "Net-(DRIVER_G2-EN_A)") (class "Default")
      (node (ref "DRIVER_G2") (pin "5") (pinfunction "EN_A_5") (pintype "passive"))
      (node (ref "DRIVER_G2") (pin "9") (pinfunction "EN_B_9") (pintype "passive"))
      (node (ref "R31") (pin "1") (pinfunction "1_1") (pintype "passive"))
    )
    (net (code "57") (name "Net-(DRIVER_G2-IN_A)") (class "Default")
      (node (ref "DRIVER_G2") (pin "4") (pinfunction "IN_A_4") (pintype "passive"))
      (node (ref "R32") (pin "2") (pinfunction "2_2") (pintype "passive"))
    )
    (net (code "58") (name "Net-(DRIVER_G2-IN_B)") (class "Default")
      (node (ref "DRIVER_G2") (pin "10") (pinfunction "IN_B_10") (pintype "passive"))
      (node (ref "R33") (pin "2") (pinfunction "2_2") (pintype "passive"))
    )
    (net (code "59") (name "Net-(DRIVER_G2-PWM)") (class "Default")
      (node (ref "DRIVER_G2") (pin "7") (pinfunction "PWM_7") (pintype "passive"))
      (node (ref "R34") (pin "2") (pinfunction "2_2") (pintype "passive"))
    )
    (net (code "60") (name "Net-(DRIVER_L1-CS)") (class "Default")
      (node (ref "DRIVER_L1") (pin "8") (pinfunction "CS_8") (pintype "passive"))
      (node (ref "R6") (pin "2") (pinfunction "2_2") (pintype "passive"))
    )
    (net (code "61") (name "Net-(DRIVER_L1-EN_A)") (class "Default")
      (node (ref "DRIVER_L1") (pin "5") (pinfunction "EN_A_5") (pintype "passive"))
      (node (ref "DRIVER_L1") (pin "9") (pinfunction "EN_B_9") (pintype "passive"))
      (node (ref "R1") (pin "1") (pinfunction "1_1") (pintype "passive"))
    )
    (net (code "62") (name "Net-(DRIVER_L1-IN_A)") (class "Default")
      (node (ref "DRIVER_L1") (pin "4") (pinfunction "IN_A_4") (pintype "passive"))
      (node (ref "R2") (pin "2") (pinfunction "2_2") (pintype "passive"))
    )
    (net (code "63") (name "Net-(DRIVER_L1-IN_B)") (class "Default")
      (node (ref "DRIVER_L1") (pin "10") (pinfunction "IN_B_10") (pintype "passive"))
      (node (ref "R3") (pin "2") (pinfunction "2_2") (pintype "passive"))
    )
    (net (code "64") (name "Net-(DRIVER_L1-PWM)") (class "Default")
      (node (ref "DRIVER_L1") (pin "7") (pinfunction "PWM_7") (pintype "passive"))
      (node (ref "R4") (pin "2") (pinfunction "2_2") (pintype "passive"))
    )
    (net (code "65") (name "Net-(DRIVER_L2-CS)") (class "Default")
      (node (ref "DRIVER_L2") (pin "8") (pinfunction "CS_8") (pintype "passive"))
      (node (ref "R12") (pin "2") (pinfunction "2_2") (pintype "passive"))
    )
    (net (code "66") (name "Net-(DRIVER_L2-EN_A)") (class "Default")
      (node (ref "DRIVER_L2") (pin "5") (pinfunction "EN_A_5") (pintype "passive"))
      (node (ref "DRIVER_L2") (pin "9") (pinfunction "EN_B_9") (pintype "passive"))
      (node (ref "R7") (pin "1") (pinfunction "1_1") (pintype "passive"))
    )
    (net (code "67") (name "Net-(DRIVER_L2-IN_A)") (class "Default")
      (node (ref "DRIVER_L2") (pin "4") (pinfunction "IN_A_4") (pintype "passive"))
      (node (ref "R8") (pin "2") (pinfunction "2_2") (pintype "passive"))
    )
    (net (code "68") (name "Net-(DRIVER_L2-IN_B)") (class "Default")
      (node (ref "DRIVER_L2") (pin "10") (pinfunction "IN_B_10") (pintype "passive"))
      (node (ref "R9") (pin "2") (pinfunction "2_2") (pintype "passive"))
    )
    (net (code "69") (name "Net-(DRIVER_L2-PWM)") (class "Default")
      (node (ref "DRIVER_L2") (pin "7") (pinfunction "PWM_7") (pintype "passive"))
      (node (ref "R10") (pin "2") (pinfunction "2_2") (pintype "passive"))
    )
    (net (code "70") (name "Net-(DRIVER_L3-CS)") (class "Default")
      (node (ref "DRIVER_L3") (pin "8") (pinfunction "CS_8") (pintype "passive"))
      (node (ref "R18") (pin "2") (pinfunction "2_2") (pintype "passive"))
    )
    (net (code "71") (name "Net-(DRIVER_L3-EN_A)") (class "Default")
      (node (ref "DRIVER_L3") (pin "5") (pinfunction "EN_A_5") (pintype "passive"))
      (node (ref "DRIVER_L3") (pin "9") (pinfunction "EN_B_9") (pintype "passive"))
      (node (ref "R13") (pin "1") (pinfunction "1_1") (pintype "passive"))
    )
    (net (code "72") (name "Net-(DRIVER_L3-IN_A)") (class "Default")
      (node (ref "DRIVER_L3") (pin "4") (pinfunction "IN_A_4") (pintype "passive"))
      (node (ref "R14") (pin "2") (pinfunction "2_2") (pintype "passive"))
    )
    (net (code "73") (name "Net-(DRIVER_L3-IN_B)") (class "Default")
      (node (ref "DRIVER_L3") (pin "10") (pinfunction "IN_B_10") (pintype "passive"))
      (node (ref "R15") (pin "2") (pinfunction "2_2") (pintype "passive"))
    )
    (net (code "74") (name "Net-(DRIVER_L3-PWM)") (class "Default")
      (node (ref "DRIVER_L3") (pin "7") (pinfunction "PWM_7") (pintype "passive"))
      (node (ref "R16") (pin "2") (pinfunction "2_2") (pintype "passive"))
    )
    (net (code "75") (name "VCC") (class "Default")
      (node (ref "5V_REG") (pin "1") (pinfunction "Vin_1") (pintype "passive"))
      (node (ref "C1") (pin "1") (pinfunction "1_1") (pintype "passive"))
      (node (ref "C10") (pin "1") (pinfunction "1_1") (pintype "passive"))
      (node (ref "C11") (pin "1") (pinfunction "1_1") (pintype "passive"))
      (node (ref "C12") (pin "1") (pinfunction "1_1") (pintype "passive"))
      (node (ref "C2") (pin "1") (pinfunction "1_1") (pintype "passive"))
      (node (ref "C3") (pin "1") (pinfunction "1_1") (pintype "passive"))
      (node (ref "C4") (pin "1") (pinfunction "1_1") (pintype "passive"))
      (node (ref "C5") (pin "1") (pinfunction "1_1") (pintype "passive"))
      (node (ref "C6") (pin "1") (pinfunction "1_1") (pintype "passive"))
      (node (ref "C7") (pin "1") (pinfunction "1_1") (pintype "passive"))
      (node (ref "C8") (pin "1") (pinfunction "1_1") (pintype "passive"))
      (node (ref "C9") (pin "1") (pinfunction "1_1") (pintype "passive"))
      (node (ref "DRIVER_BASE") (pin "13") (pinfunction "VCC_13") (pintype "passive"))
      (node (ref "DRIVER_BASE") (pin "14") (pinfunction "NC_14") (pintype "passive"))
      (node (ref "DRIVER_BASE") (pin "2") (pinfunction "NC_2") (pintype "passive"))
      (node (ref "DRIVER_BASE") (pin "23") (pinfunction "VCC_23") (pintype "passive"))
      (node (ref "DRIVER_BASE") (pin "3") (pinfunction "VCC_3") (pintype "passive"))
      (node (ref "DRIVER_G1") (pin "13") (pinfunction "VCC_13") (pintype "passive"))
      (node (ref "DRIVER_G1") (pin "14") (pinfunction "NC_14") (pintype "passive"))
      (node (ref "DRIVER_G1") (pin "2") (pinfunction "NC_2") (pintype "passive"))
      (node (ref "DRIVER_G1") (pin "23") (pinfunction "VCC_23") (pintype "passive"))
      (node (ref "DRIVER_G1") (pin "3") (pinfunction "VCC_3") (pintype "passive"))
      (node (ref "DRIVER_G2") (pin "13") (pinfunction "VCC_13") (pintype "passive"))
      (node (ref "DRIVER_G2") (pin "14") (pinfunction "NC_14") (pintype "passive"))
      (node (ref "DRIVER_G2") (pin "2") (pinfunction "NC_2") (pintype "passive"))
      (node (ref "DRIVER_G2") (pin "23") (pinfunction "VCC_23") (pintype "passive"))
      (node (ref "DRIVER_G2") (pin "3") (pinfunction "VCC_3") (pintype "passive"))
      (node (ref "DRIVER_L1") (pin "13") (pinfunction "VCC_13") (pintype "passive"))
      (node (ref "DRIVER_L1") (pin "14") (pinfunction "NC_14") (pintype "passive"))
      (node (ref "DRIVER_L1") (pin "2") (pinfunction "NC_2") (pintype "passive"))
      (node (ref "DRIVER_L1") (pin "23") (pinfunction "VCC_23") (pintype "passive"))
      (node (ref "DRIVER_L1") (pin "3") (pinfunction "VCC_3") (pintype "passive"))
      (node (ref "DRIVER_L2") (pin "13") (pinfunction "VCC_13") (pintype "passive"))
      (node (ref "DRIVER_L2") (pin "14") (pinfunction "NC_14") (pintype "passive"))
      (node (ref "DRIVER_L2") (pin "2") (pinfunction "NC_2") (pintype "passive"))
      (node (ref "DRIVER_L2") (pin "23") (pinfunction "VCC_23") (pintype "passive"))
      (node (ref "DRIVER_L2") (pin "3") (pinfunction "VCC_3") (pintype "passive"))
      (node (ref "DRIVER_L3") (pin "13") (pinfunction "VCC_13") (pintype "passive"))
      (node (ref "DRIVER_L3") (pin "14") (pinfunction "NC_14") (pintype "passive"))
      (node (ref "DRIVER_L3") (pin "2") (pinfunction "NC_2") (pintype "passive"))
      (node (ref "DRIVER_L3") (pin "23") (pinfunction "VCC_23") (pintype "passive"))
      (node (ref "DRIVER_L3") (pin "3") (pinfunction "VCC_3") (pintype "passive"))
    )
    (net (code "76") (name "VDD") (class "Default")
      (node (ref "R1") (pin "2") (pinfunction "2_2") (pintype "passive"))
      (node (ref "R13") (pin "2") (pinfunction "2_2") (pintype "passive"))
      (node (ref "R19") (pin "2") (pinfunction "2_2") (pintype "passive"))
      (node (ref "R25") (pin "2") (pinfunction "2_2") (pintype "passive"))
      (node (ref "R31") (pin "2") (pinfunction "2_2") (pintype "passive"))
      (node (ref "R7") (pin "2") (pinfunction "2_2") (pintype "passive"))
      (node (ref "TEENSY3.1") (pin "25") (pinfunction "3v3_25") (pintype "passive"))
    )
    (net (code "77") (name "unconnected-(DRIVER_BASE-CS_DIS-Pad6)") (class "Default")
      (node (ref "DRIVER_BASE") (pin "6") (pinfunction "CS_DIS_6") (pintype "passive"))
    )
    (net (code "78") (name "unconnected-(DRIVER_G1-CS_DIS-Pad6)") (class "Default")
      (node (ref "DRIVER_G1") (pin "6") (pinfunction "CS_DIS_6") (pintype "passive"))
    )
    (net (code "79") (name "unconnected-(DRIVER_G2-CS_DIS-Pad6)") (class "Default")
      (node (ref "DRIVER_G2") (pin "6") (pinfunction "CS_DIS_6") (pintype "passive"))
    )
    (net (code "80") (name "unconnected-(DRIVER_L1-CS_DIS-Pad6)") (class "Default")
      (node (ref "DRIVER_L1") (pin "6") (pinfunction "CS_DIS_6") (pintype "passive"))
    )
    (net (code "81") (name "unconnected-(DRIVER_L2-CS_DIS-Pad6)") (class "Default")
      (node (ref "DRIVER_L2") (pin "6") (pinfunction "CS_DIS_6") (pintype "passive"))
    )
    (net (code "82") (name "unconnected-(DRIVER_L3-CS_DIS-Pad6)") (class "Default")
      (node (ref "DRIVER_L3") (pin "6") (pinfunction "CS_DIS_6") (pintype "passive"))
    )
    (net (code "83") (name "unconnected-(TEENSY3.1-A8-Pad23)") (class "Default")
      (node (ref "TEENSY3.1") (pin "23") (pinfunction "A8_23") (pintype "passive"))
    )
    (net (code "84") (name "unconnected-(TEENSY3.1-A9-Pad24)") (class "Default")
      (node (ref "TEENSY3.1") (pin "24") (pinfunction "A9_24") (pintype "passive"))
    )
    (net (code "85") (name "unconnected-(TEENSY3.1-AG-Pad26)") (class "Default")
      (node (ref "TEENSY3.1") (pin "26") (pinfunction "AG_26") (pintype "passive"))
    )
  )
)
